# design.net
KiCad netlist of a schematic drawn in EasyEDA Pro
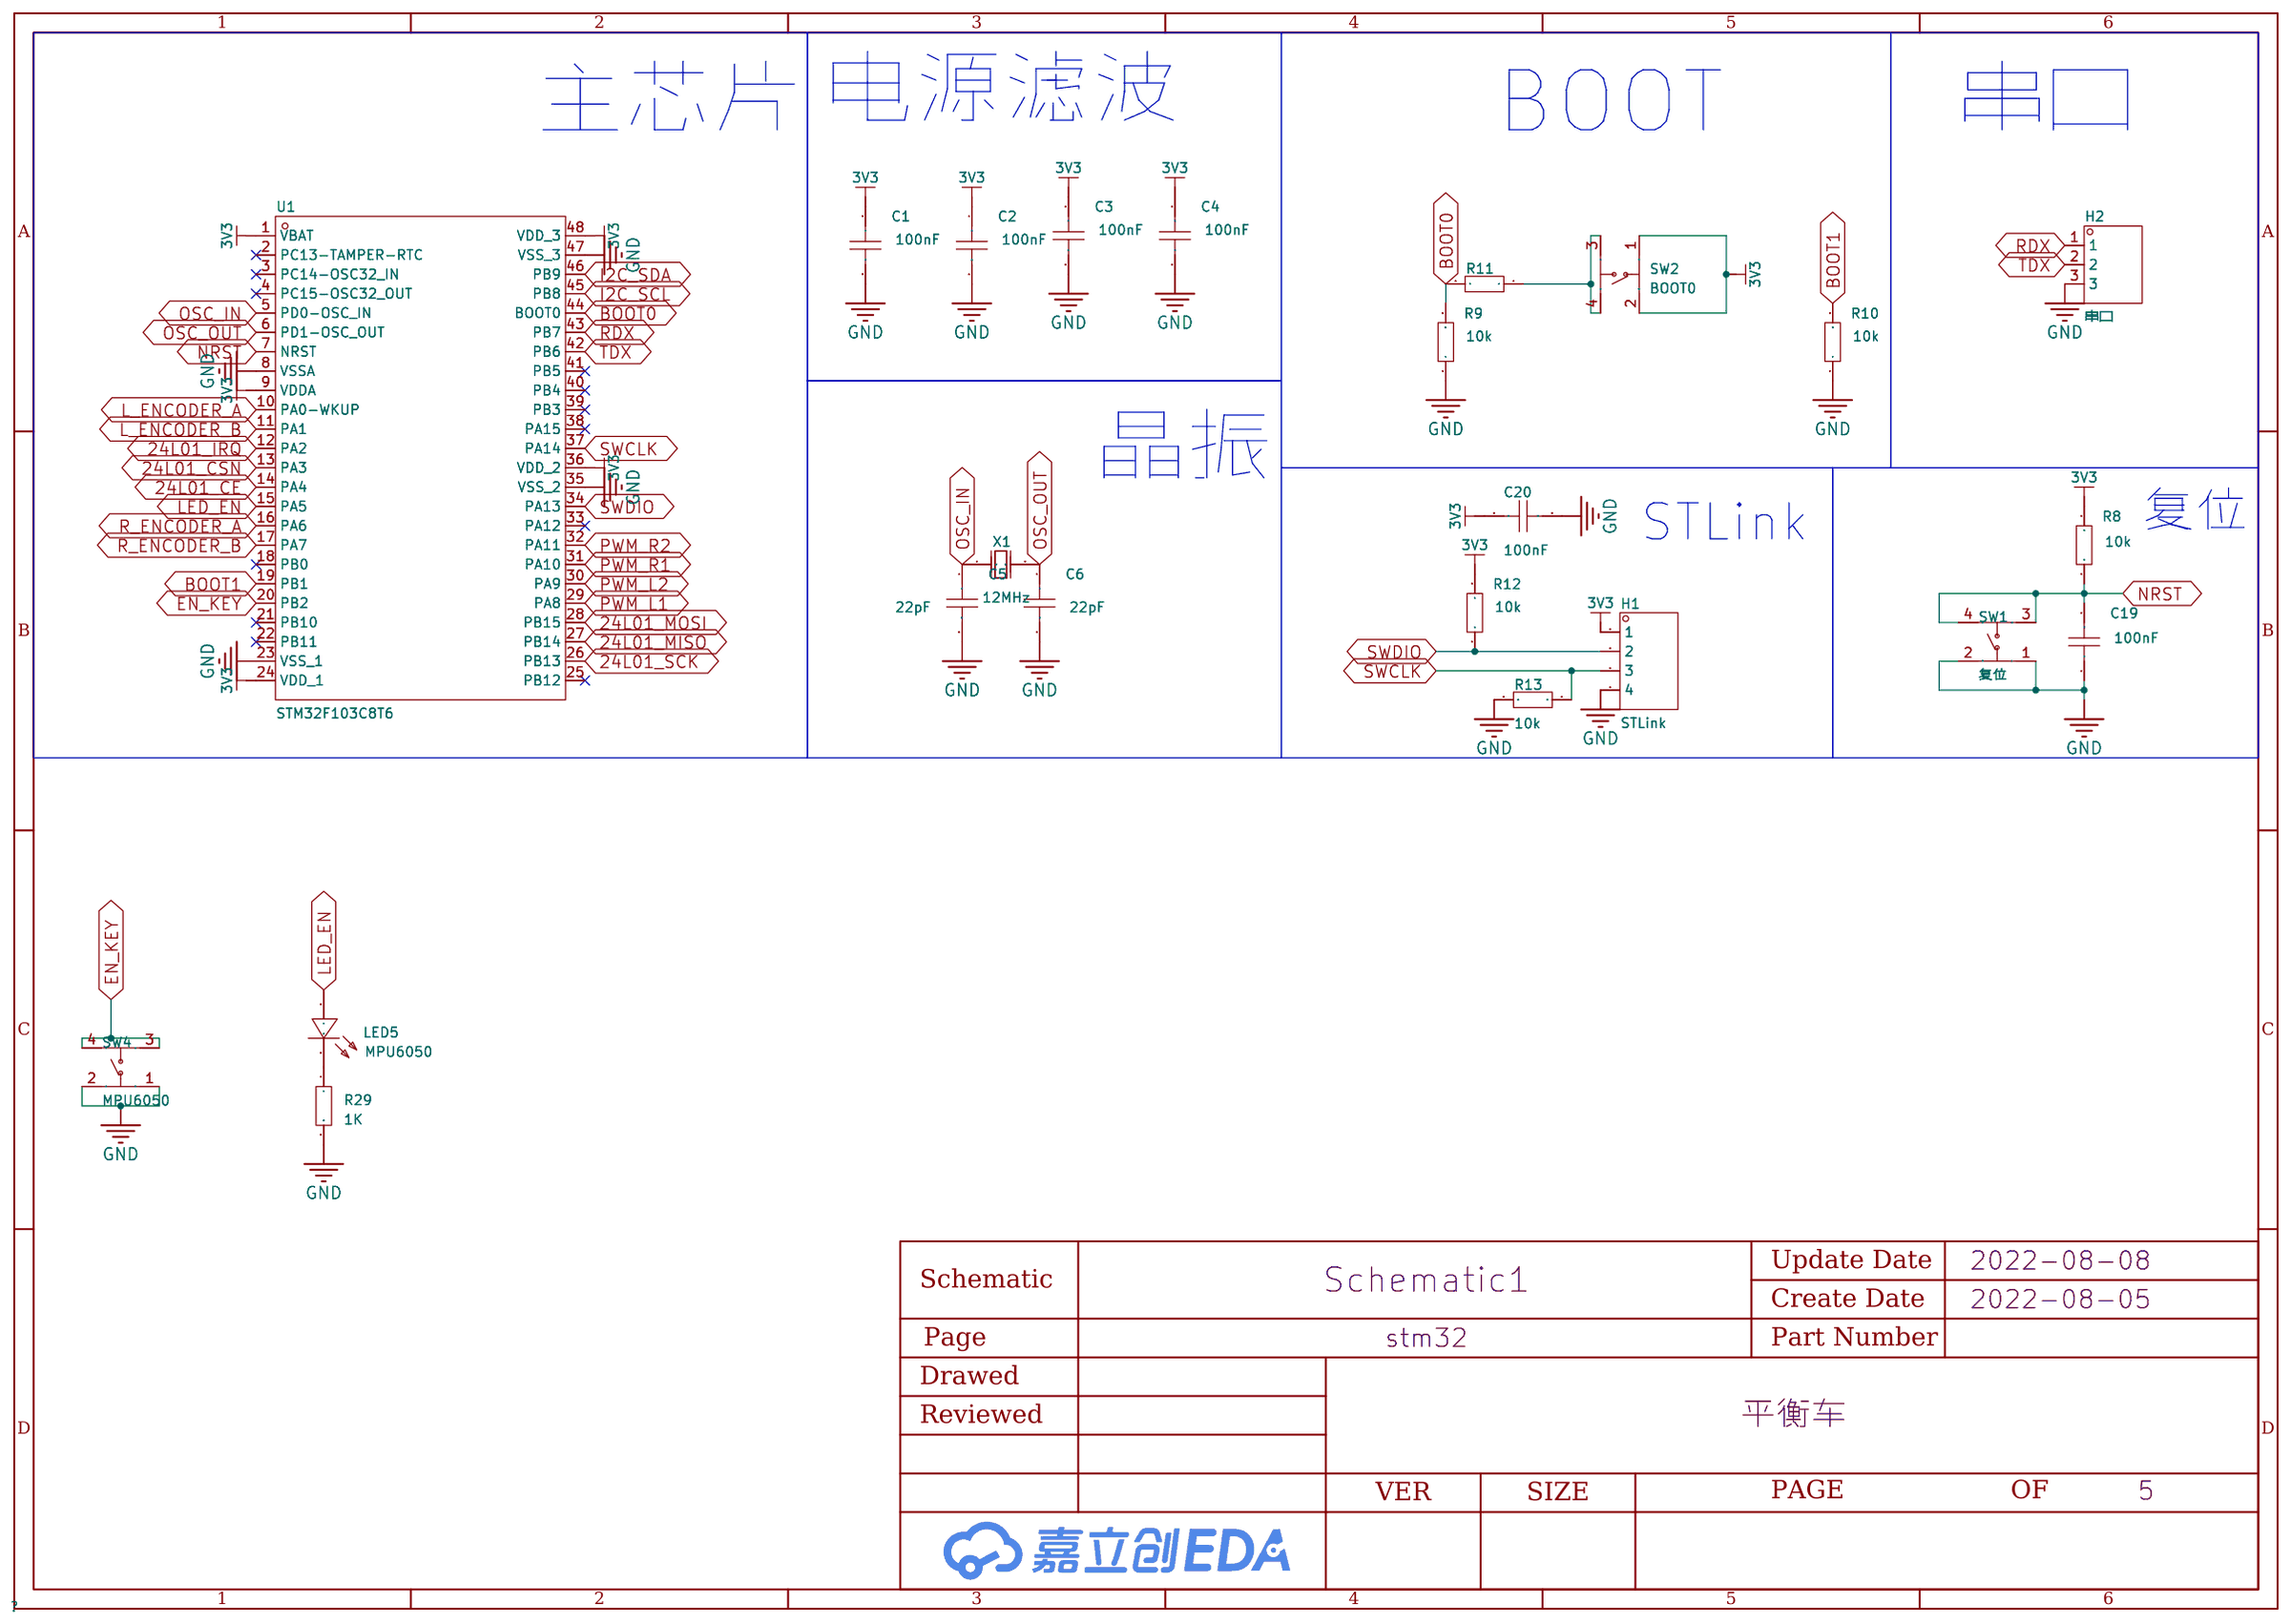
[diagram p0: stm32]
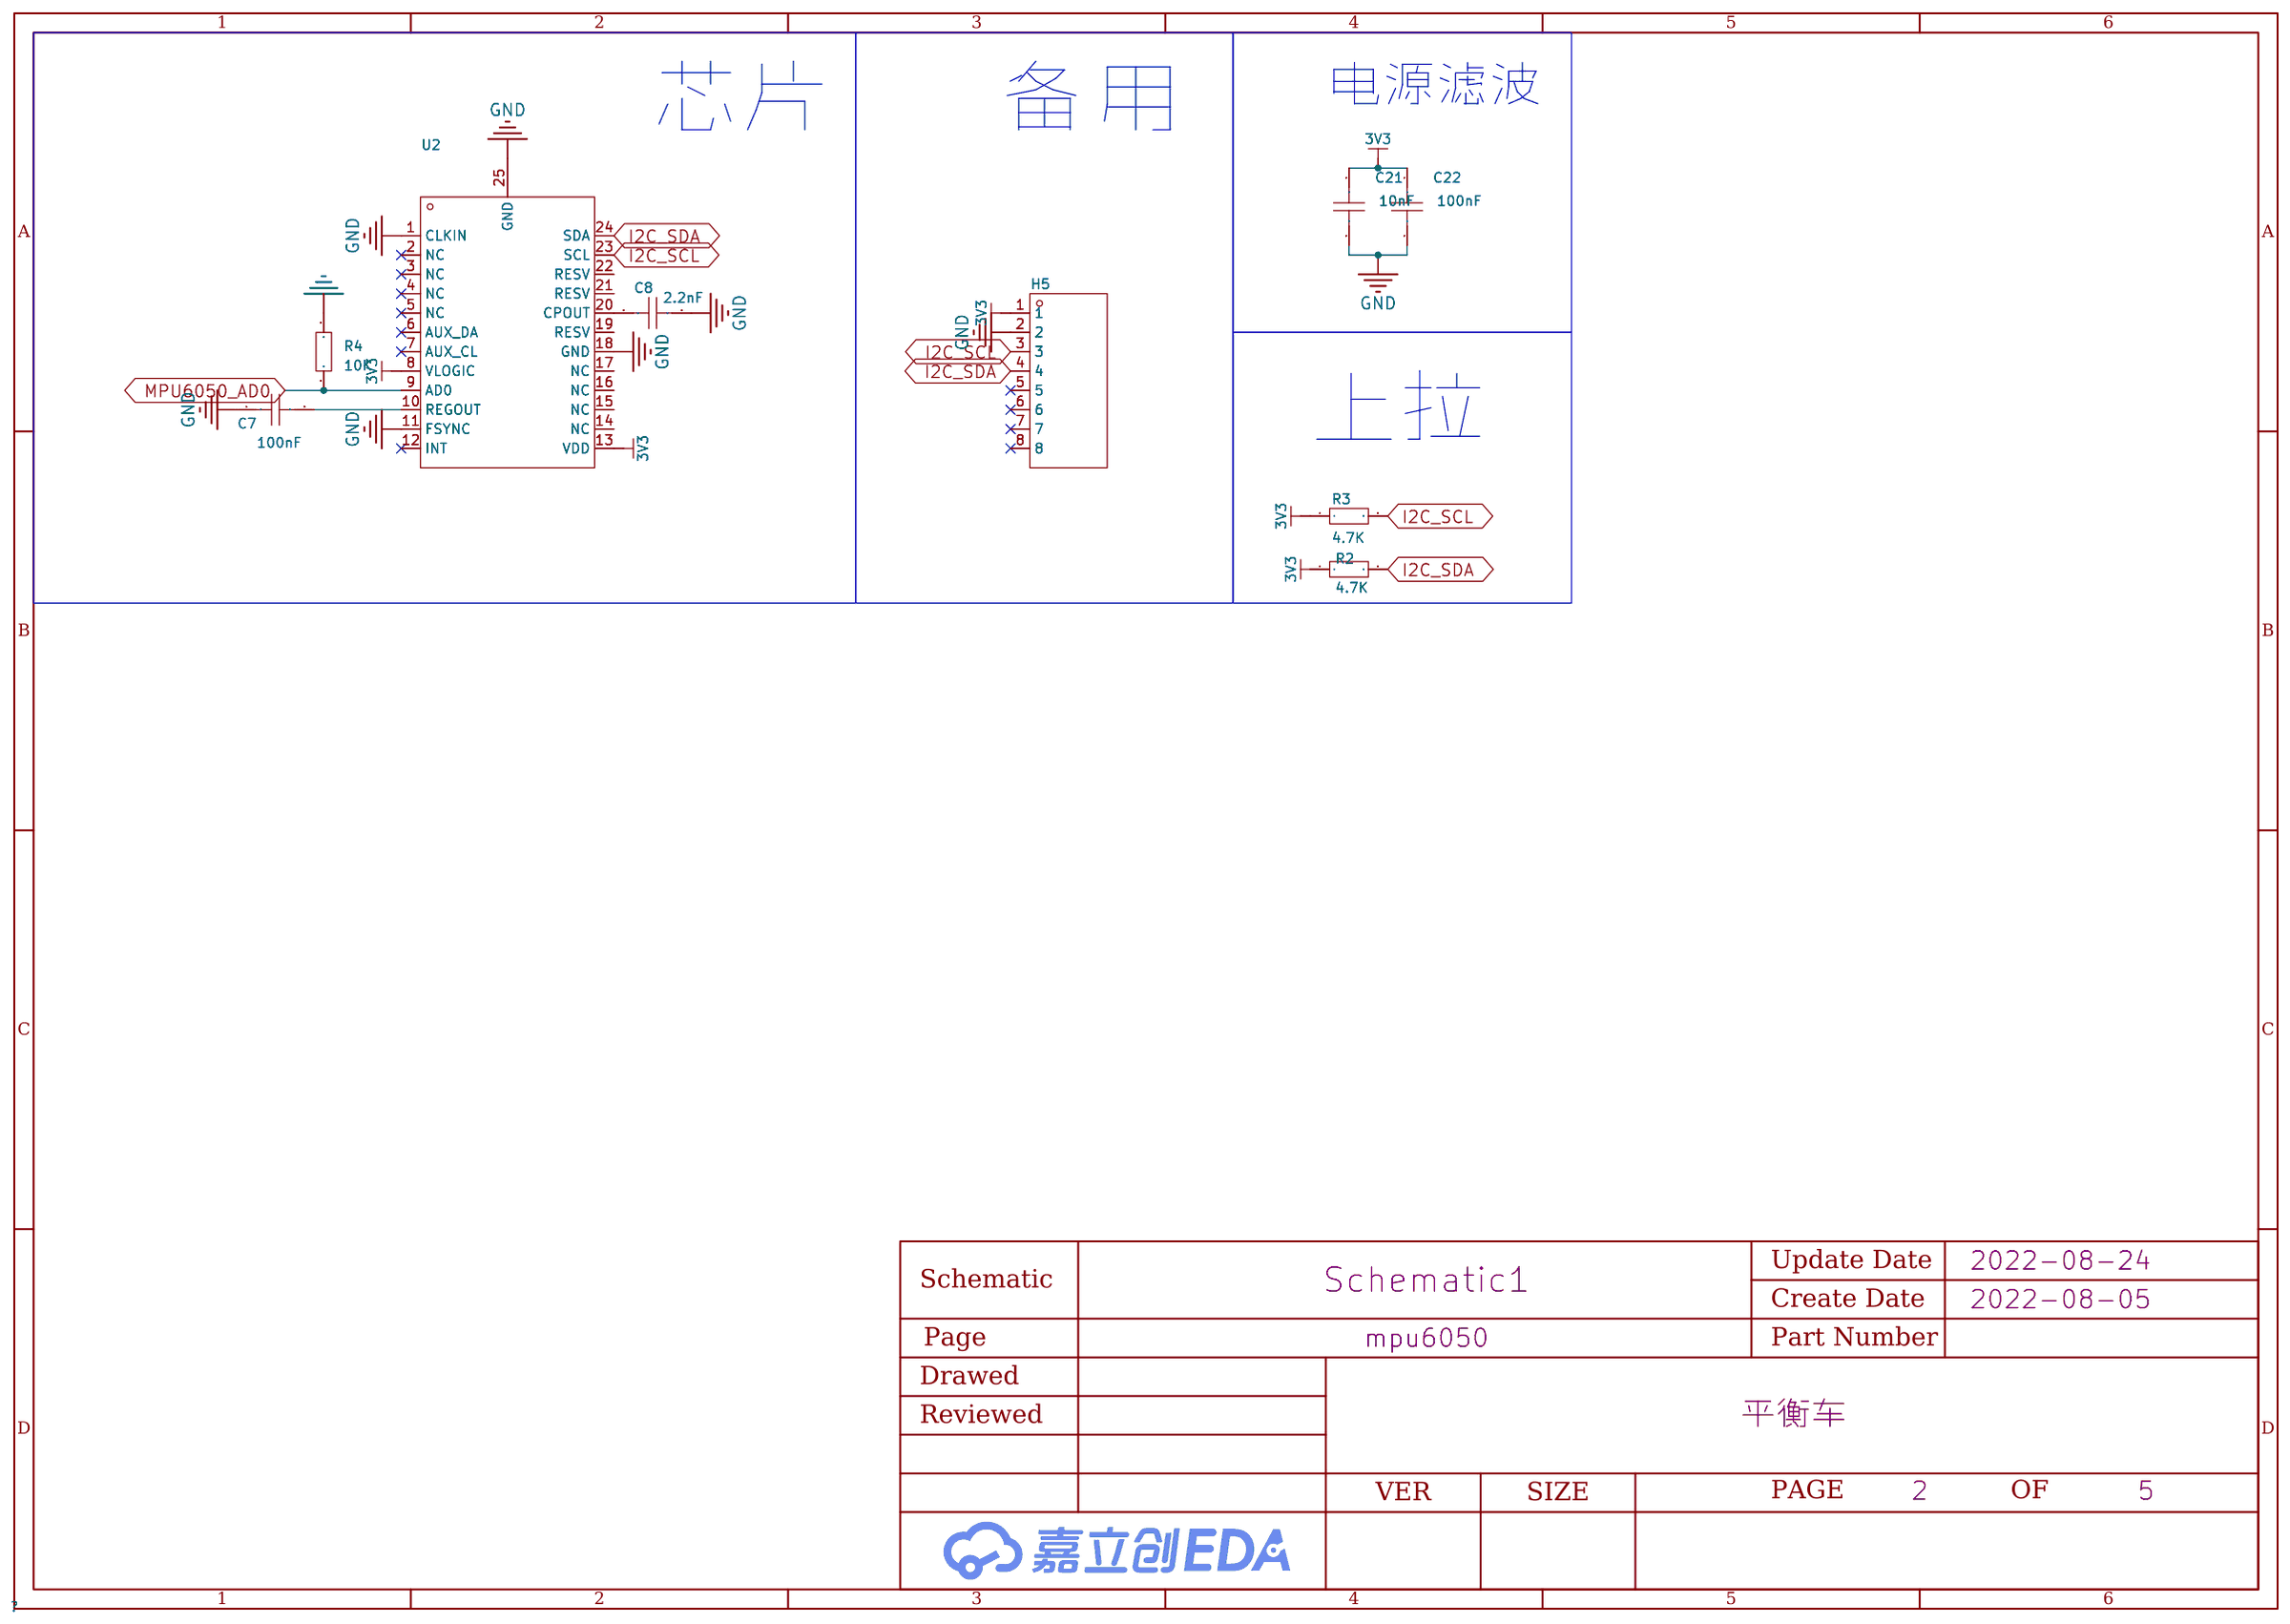
[diagram p1: mpu6050]
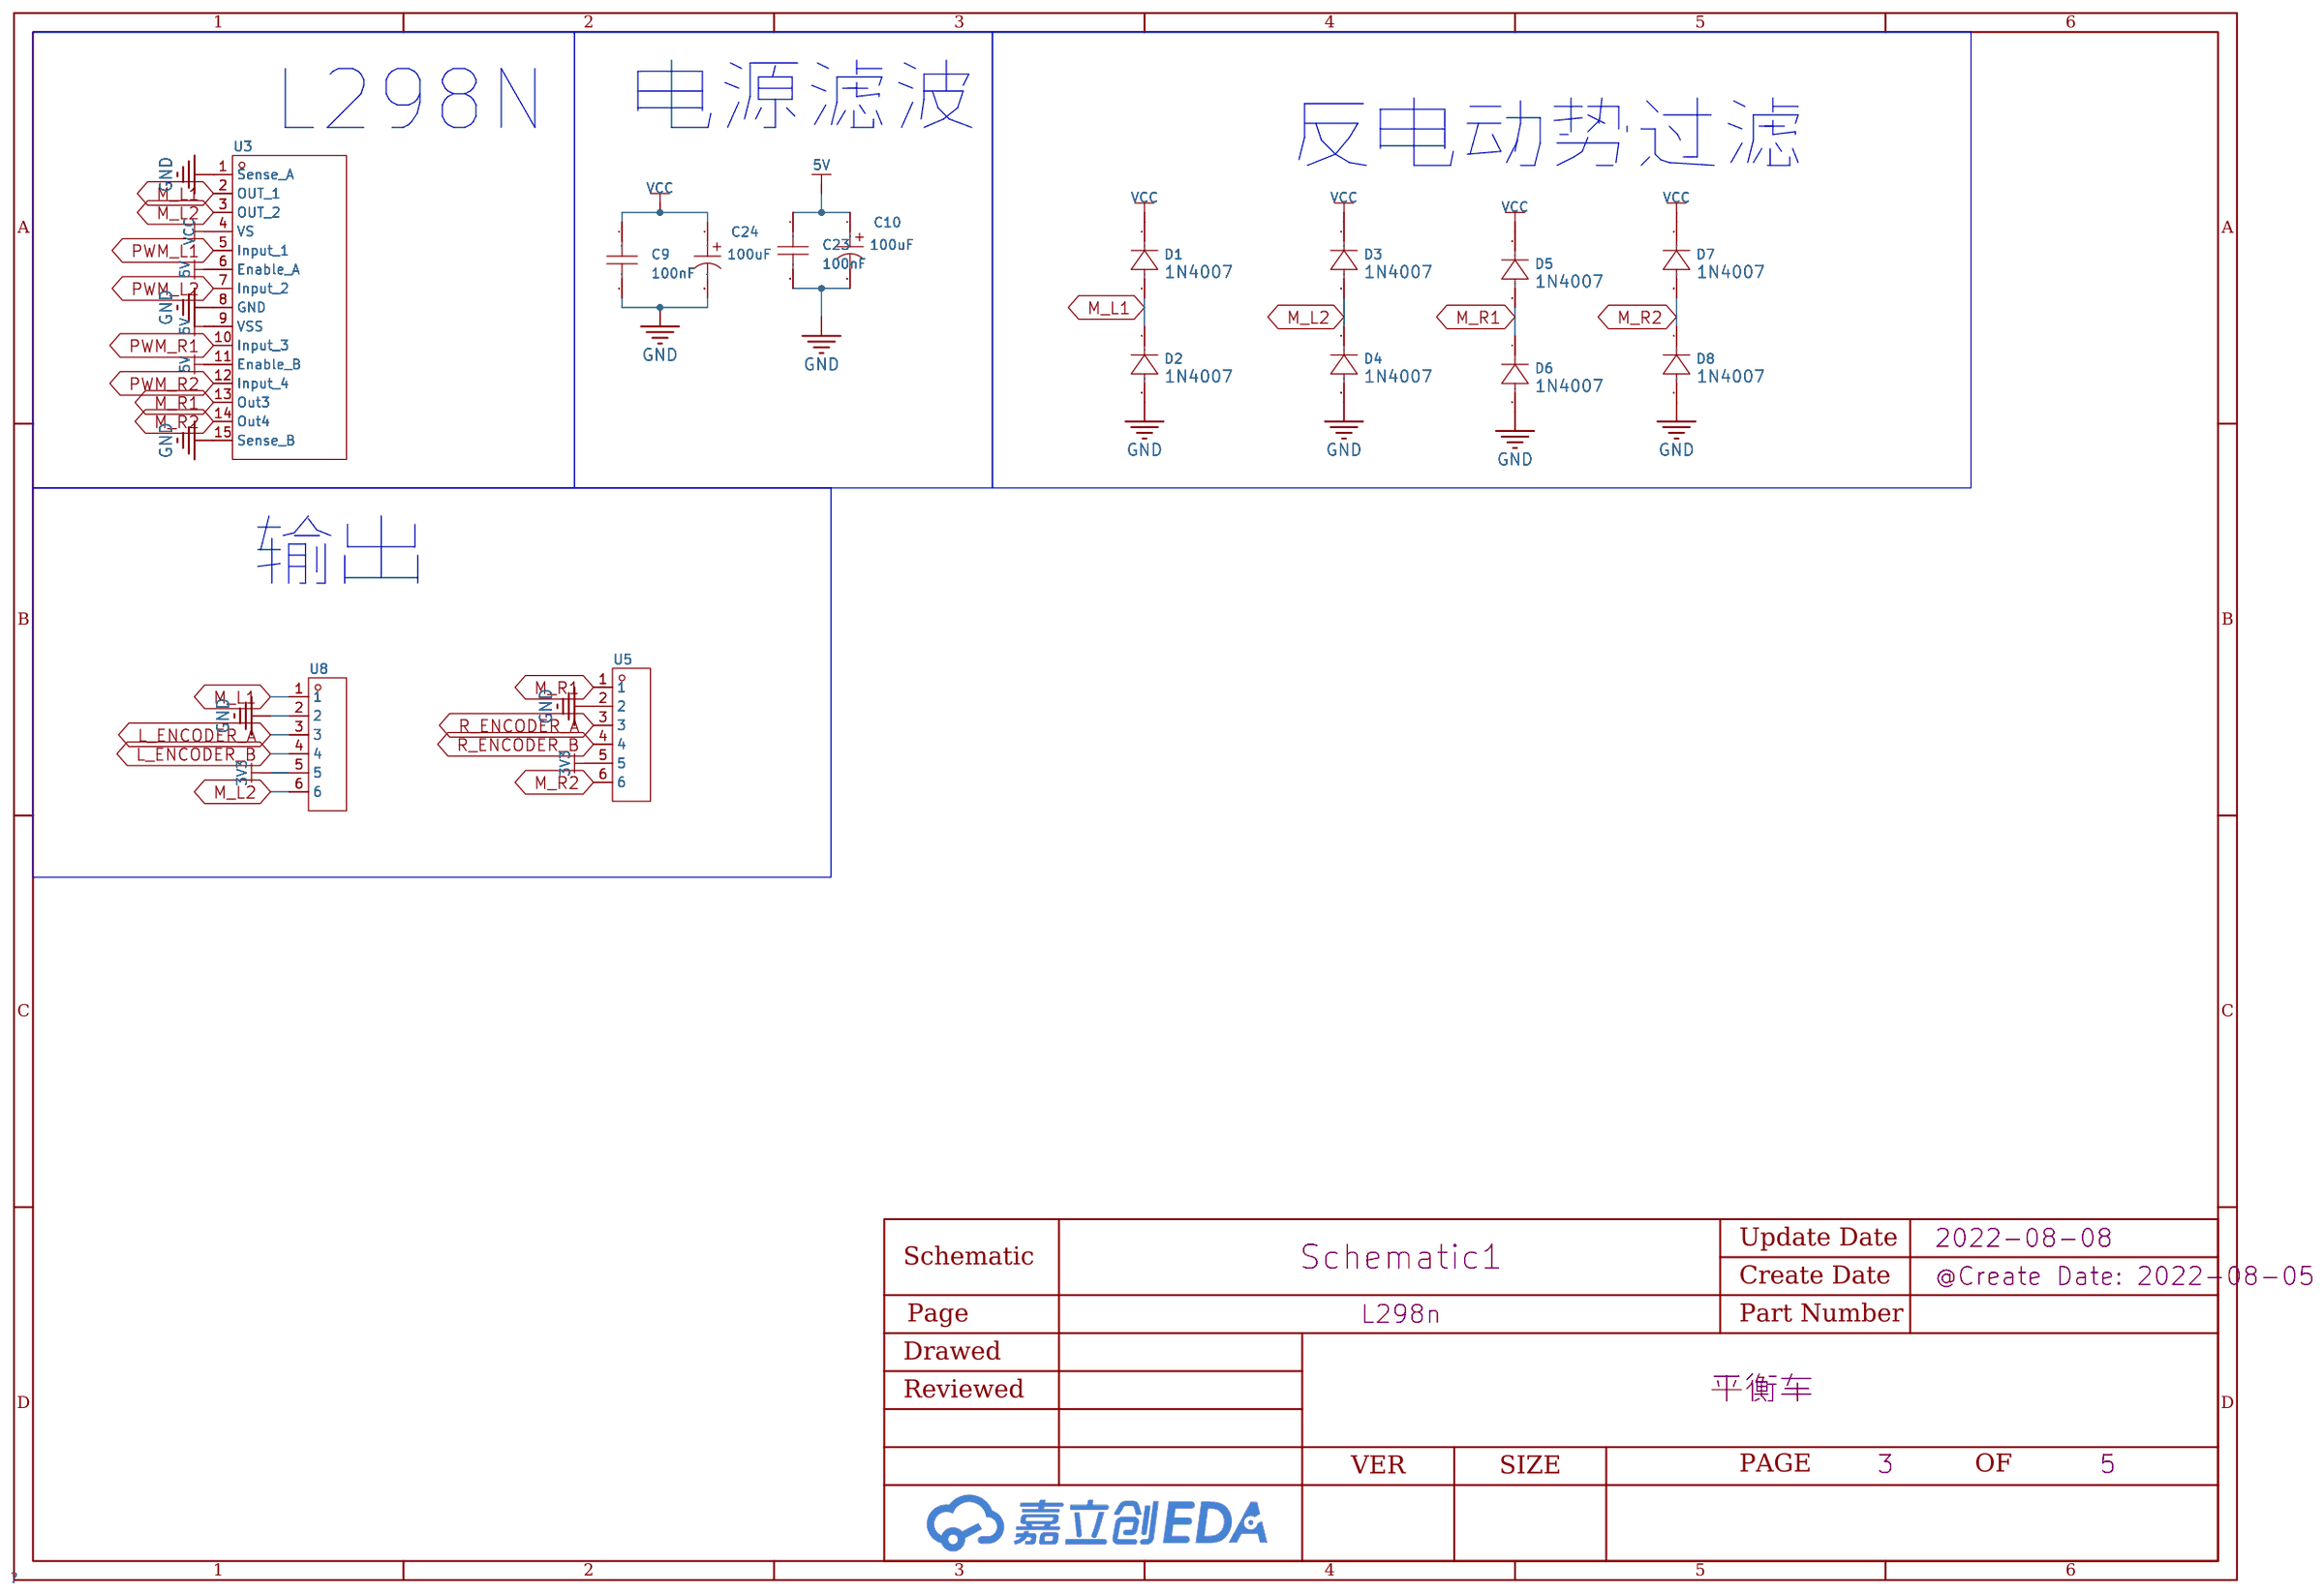
[diagram p2: L298n]
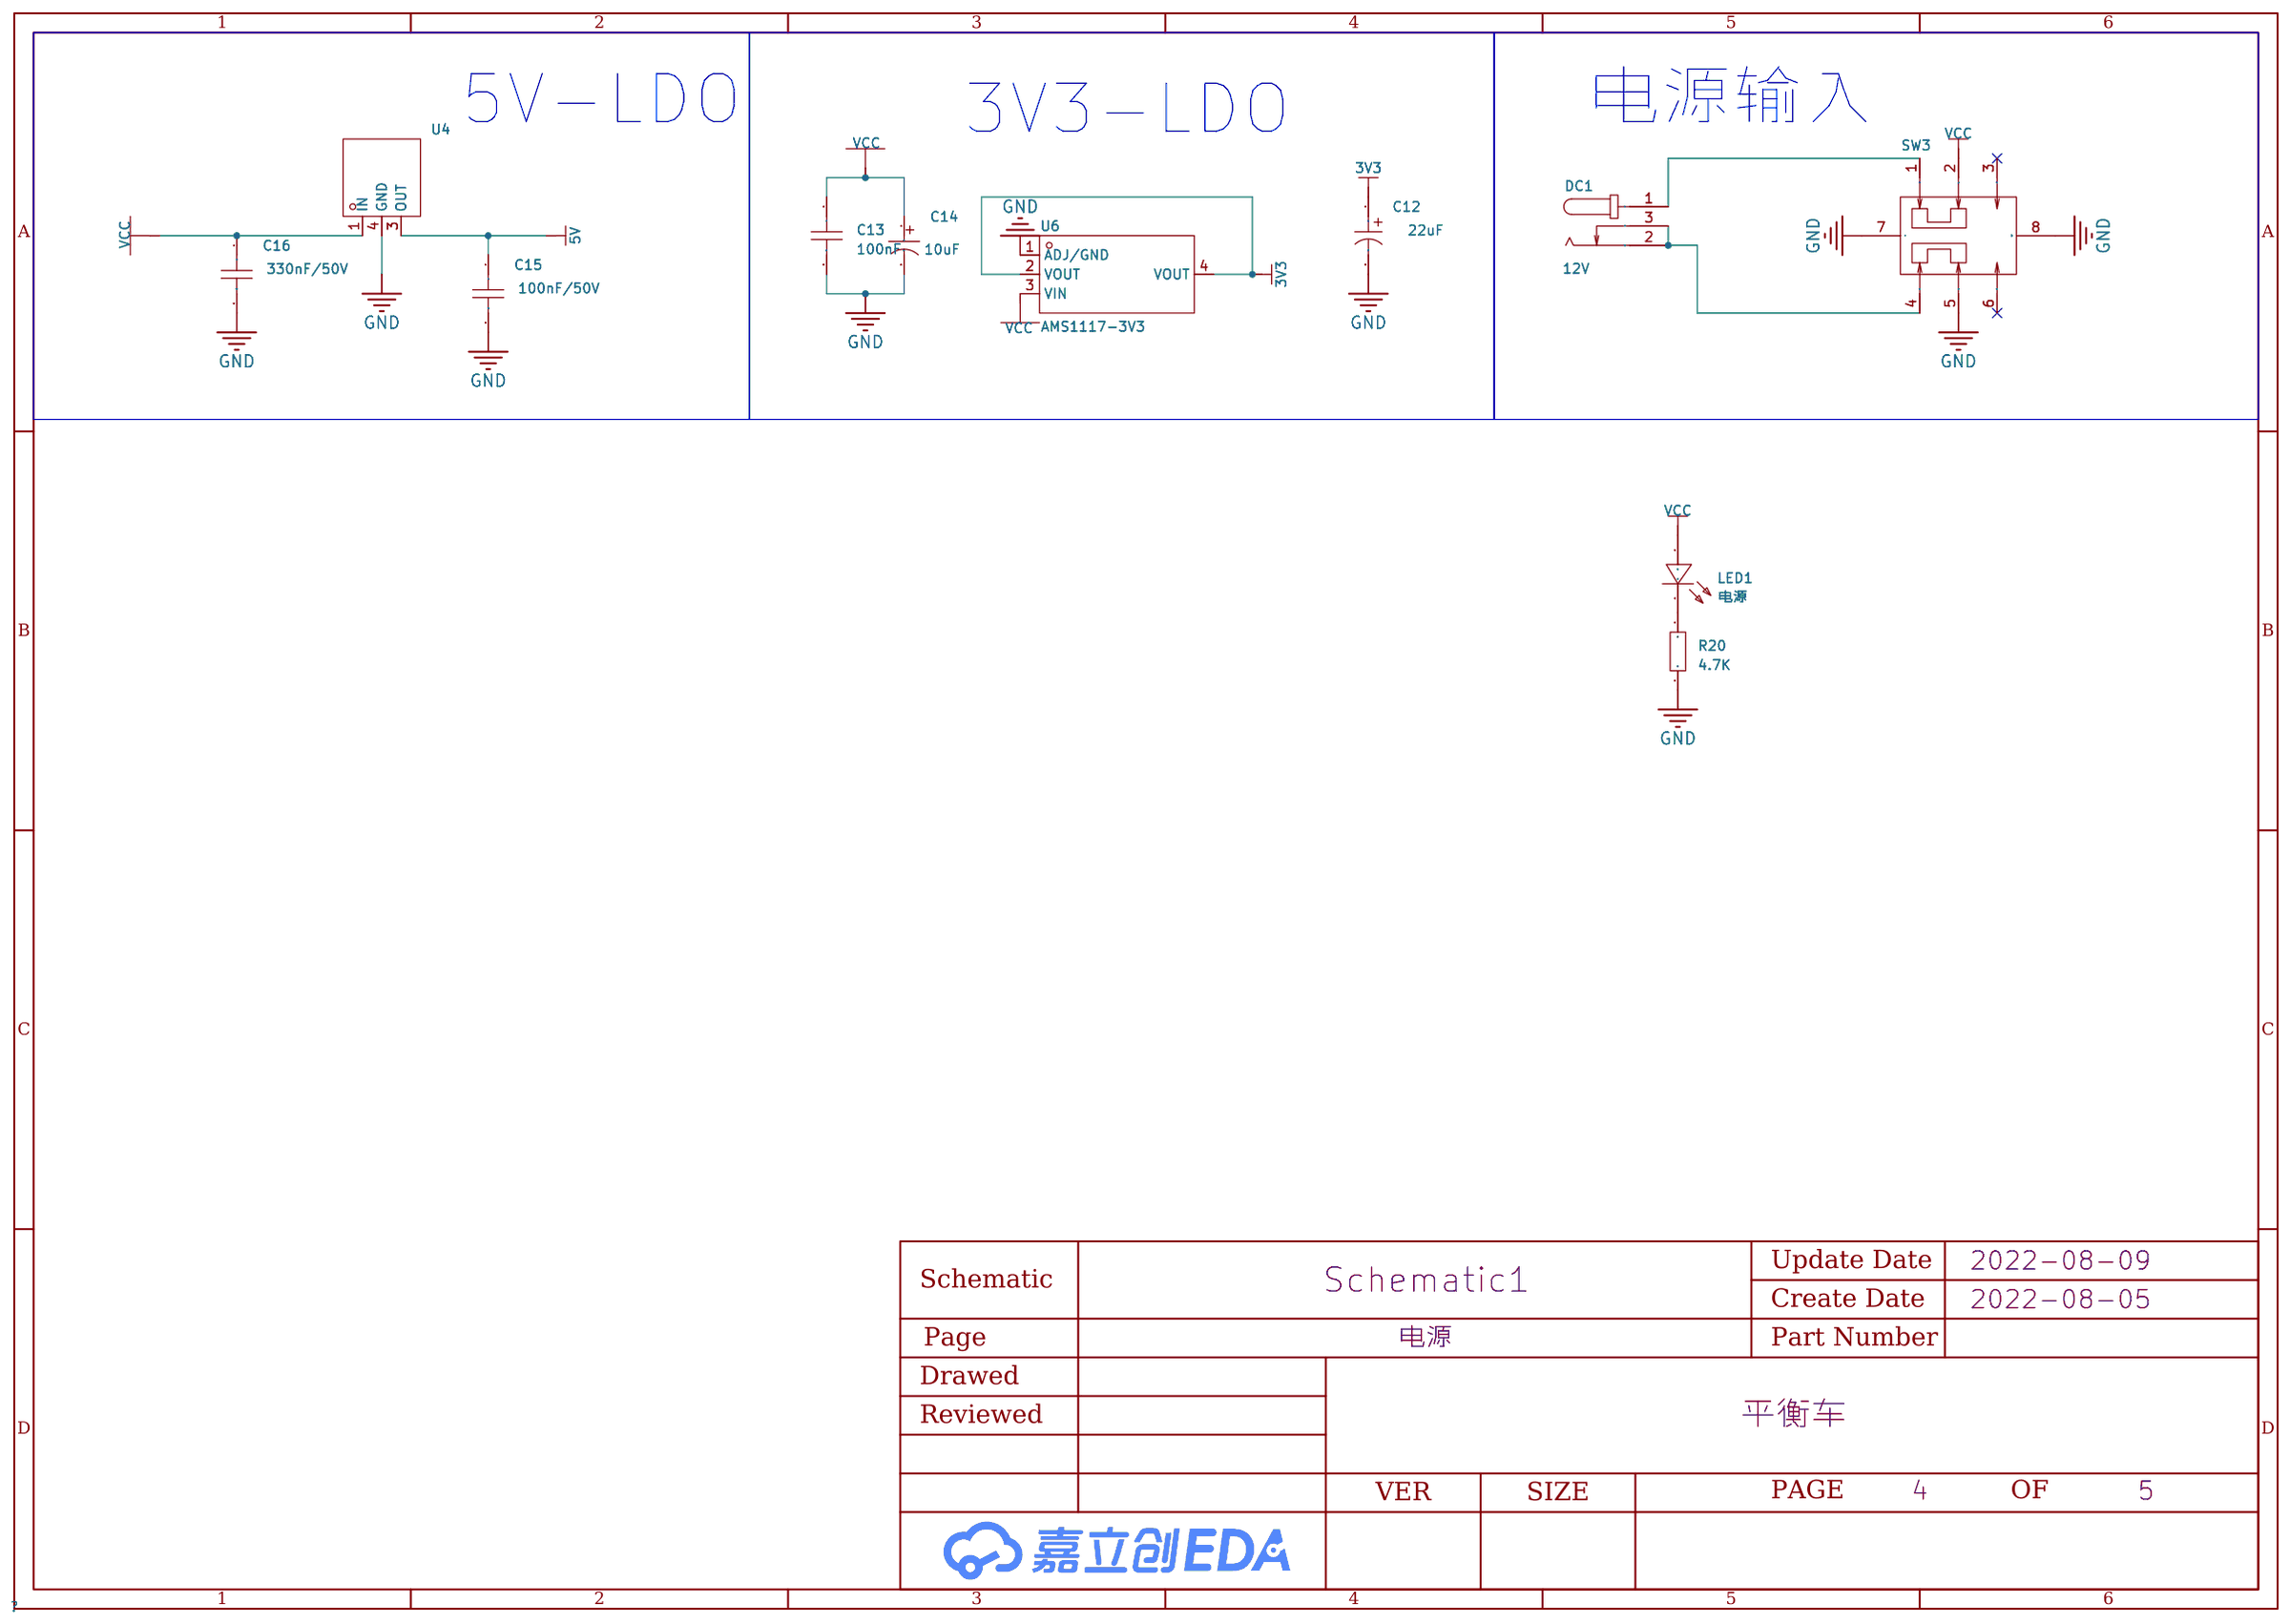
[diagram p3: 电源]
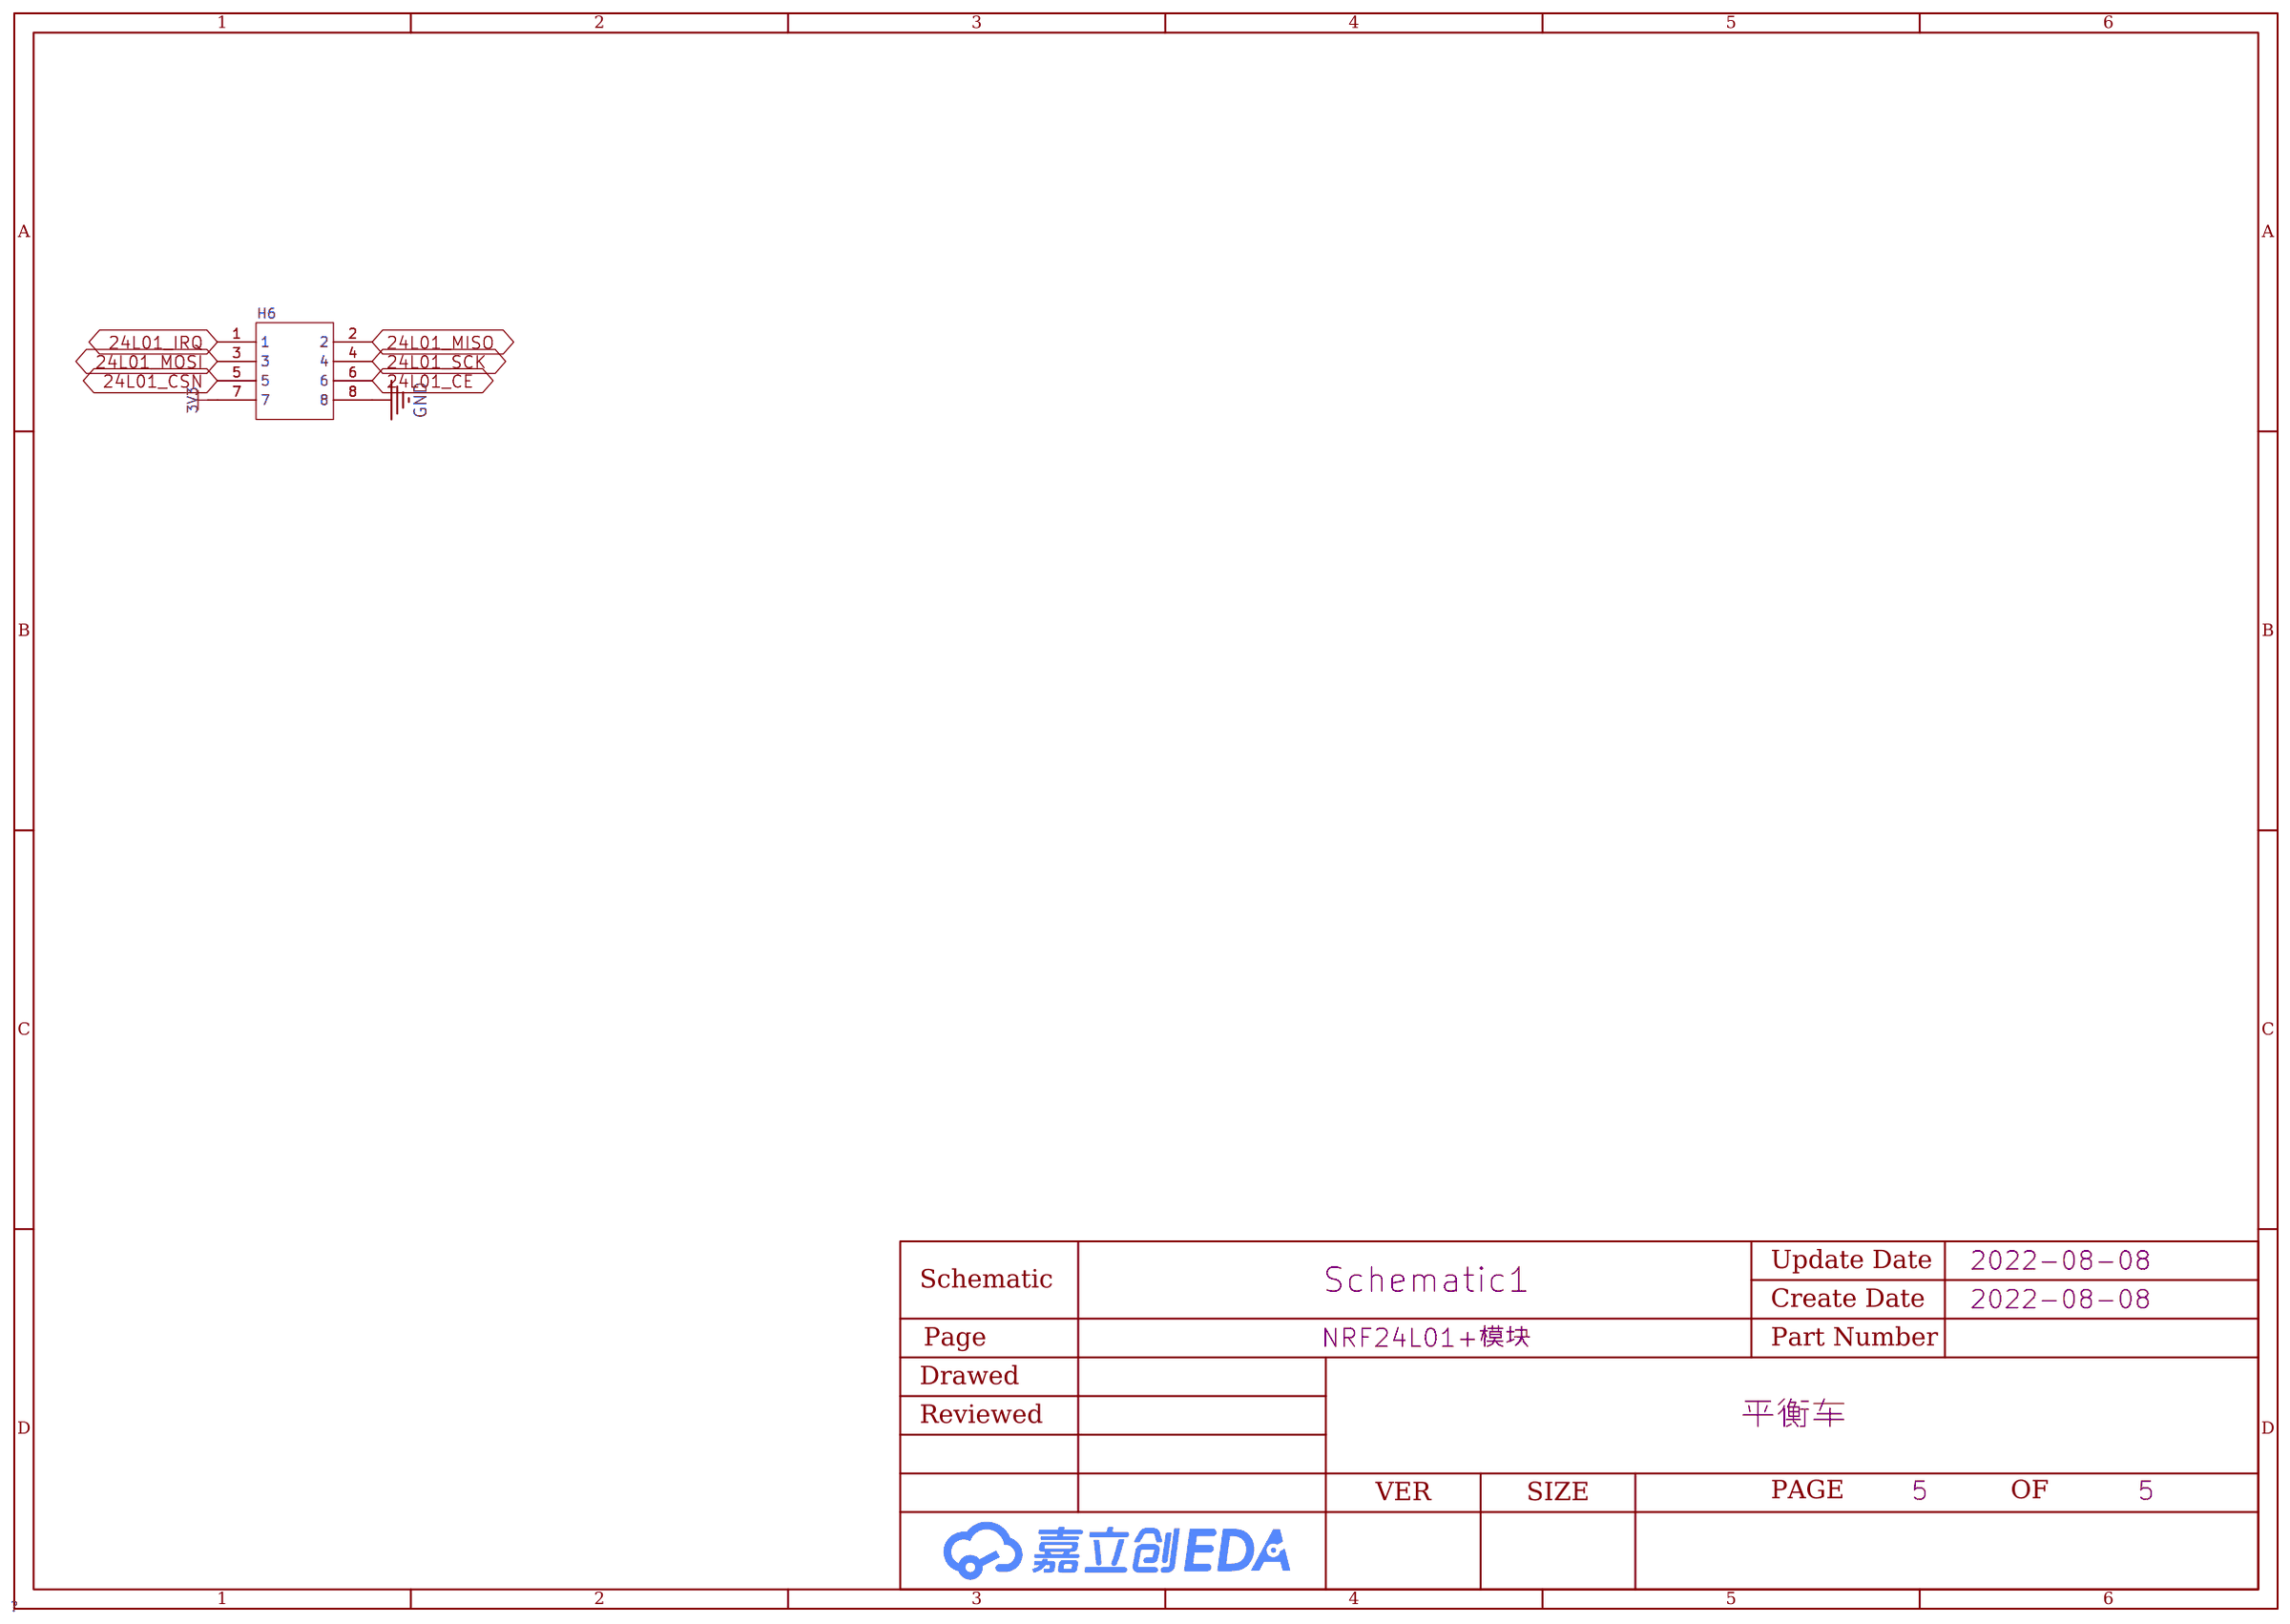
[diagram p4: NRF24L01+模块]

(export (version "E")
  (design (tool "Eeschema 10.0.6"))
  (components
    (comp (ref "C1")
      (value "100nF")
      (footprint "easyedapro:C0805")
      (fields (field (name "Manufacturer Part") "0805"))
      (libsource (lib "easyedapro") (part "0805_C9900012713"))
    )
    (comp (ref "C2")
      (value "100nF")
      (footprint "easyedapro:C0805")
      (fields (field (name "Manufacturer Part") "0805"))
      (libsource (lib "easyedapro") (part "0805_C9900012713"))
    )
    (comp (ref "C3")
      (value "100nF")
      (footprint "easyedapro:C0805")
      (fields (field (name "Manufacturer Part") "0805"))
      (libsource (lib "easyedapro") (part "0805_C9900012713"))
    )
    (comp (ref "C4")
      (value "100nF")
      (footprint "easyedapro:C0805")
      (fields (field (name "Manufacturer Part") "0805"))
      (libsource (lib "easyedapro") (part "0805_C9900012713"))
    )
    (comp (ref "C5")
      (value "22pF")
      (footprint "easyedapro:C0805")
      (fields (field (name "Manufacturer Part") "0805"))
      (libsource (lib "easyedapro") (part "0805_C9900012713"))
    )
    (comp (ref "C6")
      (value "22pF")
      (footprint "easyedapro:C0805")
      (fields (field (name "Manufacturer Part") "0805"))
      (libsource (lib "easyedapro") (part "0805_C9900012713"))
    )
    (comp (ref "C19")
      (value "100nF")
      (footprint "easyedapro:C0805")
      (fields (field (name "Manufacturer Part") "0805"))
      (libsource (lib "easyedapro") (part "0805_C9900012713"))
    )
    (comp (ref "C20")
      (value "100nF")
      (footprint "easyedapro:C0805")
      (fields (field (name "Manufacturer Part") "0805"))
      (libsource (lib "easyedapro") (part "0805_C9900012713"))
    )
    (comp (ref "H1")
      (value "STLink")
      (footprint "easyedapro:HDR-TH_4P-P2.54-V-M")
      (fields (field (name "Manufacturer Part") "B-2100S04P-A110") (field (name "Manufacturer") "Ckmtw(灿科盟)"))
      (libsource (lib "easyedapro") (part "Header-Male-2.54_1x4"))
    )
    (comp (ref "H2")
      (value "串口")
      (footprint "easyedapro:HDR-TH_3P-P2.54-V-M-1")
      (fields (field (name "Manufacturer Part") "77311-102-03LF") (field (name "Manufacturer") "Amphenol"))
      (libsource (lib "easyedapro") (part "77311-102-03LF"))
    )
    (comp (ref "LED5")
      (value "MPU6050")
      (footprint "easyedapro:LED0805-R-RD")
      (description "发光颜色:翠绿;")
      (fields (field (name "Manufacturer Part") "NCD0805G1") (field (name "Manufacturer") "国星光电"))
      (libsource (lib "easyedapro") (part "FC-2012UGK-520D5"))
    )
    (comp (ref "R8")
      (value "10k")
      (footprint "easyedapro:R0805")
      (fields (field (name "Manufacturer Part") "0805"))
      (libsource (lib "easyedapro") (part "0805"))
    )
    (comp (ref "R9")
      (value "10k")
      (footprint "easyedapro:R0805")
      (fields (field (name "Manufacturer Part") "0805"))
      (libsource (lib "easyedapro") (part "0805"))
    )
    (comp (ref "R10")
      (value "10k")
      (footprint "easyedapro:R0805")
      (fields (field (name "Manufacturer Part") "0805"))
      (libsource (lib "easyedapro") (part "0805"))
    )
    (comp (ref "R11")
      (value "100R")
      (footprint "easyedapro:R0805")
      (fields (field (name "Manufacturer Part") "0805"))
      (libsource (lib "easyedapro") (part "0805"))
    )
    (comp (ref "R12")
      (value "10k")
      (footprint "easyedapro:R0805")
      (fields (field (name "Manufacturer Part") "0805"))
      (libsource (lib "easyedapro") (part "0805"))
    )
    (comp (ref "R13")
      (value "10k")
      (footprint "easyedapro:R0805")
      (fields (field (name "Manufacturer Part") "0805"))
      (libsource (lib "easyedapro") (part "0805"))
    )
    (comp (ref "R29")
      (value "1K")
      (footprint "easyedapro:R0805")
      (fields (field (name "Manufacturer Part") "0805"))
      (libsource (lib "easyedapro") (part "0805"))
    )
    (comp (ref "SW1")
      (value "复位")
      (footprint "easyedapro:SW-SMD_4P-L6.0-W6.0-P4.50-LS9.0-2")
      (fields
        (field (name "Manufacturer Part") "KH-6X6X5H-STM")
        (field (name "Manufacturer") "kinghelm(金航标)")
      )
      (libsource (lib "easyedapro") (part "KH-6X6X5H-STM"))
    )
    (comp (ref "SW2")
      (value "BOOT0")
      (footprint "easyedapro:SW-SMD_4P-L6.0-W6.0-P4.50-LS9.0-2")
      (fields
        (field (name "Manufacturer Part") "KH-6X6X5H-STM")
        (field (name "Manufacturer") "kinghelm(金航标)")
      )
      (libsource (lib "easyedapro") (part "KH-6X6X5H-STM"))
    )
    (comp (ref "SW4")
      (value "MPU6050")
      (footprint "easyedapro:SW-SMD_4P-L6.0-W6.0-P4.50-LS9.0-2")
      (fields
        (field (name "Manufacturer Part") "KH-6X6X5H-STM")
        (field (name "Manufacturer") "kinghelm(金航标)")
      )
      (libsource (lib "easyedapro") (part "KH-6X6X5H-STM"))
    )
    (comp (ref "U1")
      (value "STM32F103C8T6")
      (footprint "easyedapro:LQFP-48_L7.0-W7.0-P0.50-LS9.0-BL")
      (description "CPU位数:32-Bit;ROM类型:FLASH;CPU内核:ARM® Cortex®-M3;主频（MAX):72MHz;工作电压:2V ~ 3.6V;")
      (fields (field (name "Manufacturer") "ST(意法半导体)"))
      (libsource (lib "easyedapro") (part "STM32F103C8T6"))
    )
    (comp (ref "X1")
      (value "12MHz")
      (footprint "easyedapro:HC-49S_L11.4-W4.8")
      (description "晶振类型:-;频率:-;频率公差:-;负载电容:-;工作温度:-;")
      (fields (field (name "Manufacturer Part") "HCM4916000000ABJT") (field (name "Manufacturer") "CITIZEN"))
      (libsource (lib "easyedapro") (part "HCM4916000000ABJT"))
    )
    (comp (ref "C7")
      (value "100nF")
      (footprint "easyedapro:C0805")
      (fields (field (name "Manufacturer Part") "0805"))
      (libsource (lib "easyedapro") (part "0805_C9900012713"))
    )
    (comp (ref "C8")
      (value "2.2nF")
      (footprint "easyedapro:C0805")
      (fields (field (name "Manufacturer Part") "0805"))
      (libsource (lib "easyedapro") (part "0805_C9900012713"))
    )
    (comp (ref "C21")
      (value "10nF")
      (footprint "easyedapro:C0805")
      (fields (field (name "Manufacturer Part") "0805"))
      (libsource (lib "easyedapro") (part "0805_C9900012713"))
    )
    (comp (ref "C22")
      (value "100nF")
      (footprint "easyedapro:C0805")
      (fields (field (name "Manufacturer Part") "0805"))
      (libsource (lib "easyedapro") (part "0805_C9900012713"))
    )
    (comp (ref "H5")
      (value "A2541HWV-8P")
      (footprint "easyedapro:HDR-TH_8P-P2.54-V_A2541HWV-8P")
      (description "间距:2.54mm;总孔位数:8;排数:1;插孔结构:1x8P;行距:-;安装类型:直插;塑高:-;触头材质:黄铜;触头镀层:金;")
      (fields (field (name "Manufacturer") "CJT(长江连接器)"))
      (libsource (lib "easyedapro") (part "A2541HWV-8P"))
    )
    (comp (ref "R2")
      (value "4.7K")
      (footprint "easyedapro:R0805")
      (fields (field (name "Manufacturer Part") "0805"))
      (libsource (lib "easyedapro") (part "0805"))
    )
    (comp (ref "R3")
      (value "4.7K")
      (footprint "easyedapro:R0805")
      (fields (field (name "Manufacturer Part") "0805"))
      (libsource (lib "easyedapro") (part "0805"))
    )
    (comp (ref "R4")
      (value "10K")
      (footprint "easyedapro:R0805")
      (fields (field (name "Manufacturer Part") "0805"))
      (libsource (lib "easyedapro") (part "0805"))
    )
    (comp (ref "U2")
      (value "~")
      (footprint "easyedapro:QFN-24_L4.0-W4.0-P0.50-BL-EP2.7")
      (description "三轴加速度计和三轴陀螺仪，工作电压：2.375V~3.46V")
      (fields
        (field (name "Manufacturer Part") "MPU-6050")
        (field (name "Manufacturer") "TDK InvenSense(应美盛)")
      )
      (libsource (lib "easyedapro") (part "MPU-6050_C24112"))
    )
    (comp (ref "C9")
      (value "100nF")
      (footprint "easyedapro:C0805")
      (fields (field (name "Manufacturer Part") "0805"))
      (libsource (lib "easyedapro") (part "0805_C9900012713"))
    )
    (comp (ref "C10")
      (value "100uF")
      (footprint "easyedapro:CAP-TH_BD8.0-P3.50-D0.6-FD")
      (description "容值:100uF;精度:-;额定电压:50V;电容体直径:-;电容体长度:-;脚间距:-;纹波电流:-;等效串联电阻:-;工作寿命:-;工作温度:-;")
      (fields (field (name "Manufacturer Part") "EEUFR1H101B") (field (name "Manufacturer") "PANASONIC(松下)"))
      (libsource (lib "easyedapro") (part "EEUFR1H101B"))
    )
    (comp (ref "C23")
      (value "100nF")
      (footprint "easyedapro:C0805")
      (fields (field (name "Manufacturer Part") "0805"))
      (libsource (lib "easyedapro") (part "0805_C9900012713"))
    )
    (comp (ref "C24")
      (value "100uF")
      (footprint "easyedapro:CAP-TH_BD8.0-P3.50-D0.6-FD")
      (description "容值:100uF;精度:-;额定电压:50V;电容体直径:-;电容体长度:-;脚间距:-;纹波电流:-;等效串联电阻:-;工作寿命:-;工作温度:-;")
      (fields (field (name "Manufacturer Part") "EEUFR1H101B") (field (name "Manufacturer") "PANASONIC(松下)"))
      (libsource (lib "easyedapro") (part "EEUFR1H101B"))
    )
    (comp (ref "D1")
      (value "1N4007")
      (footprint "easyedapro:SMA_L4.4-W2.8-LS5.4-RD")
      (description "二极管配置:独立式;直流反向耐压(Vr):1kV;平均整流电流(Io):1A;正向压降(Vf):1.1V@1A;反向电流(Ir):5A@1kV;")
      (fields (field (name "Manufacturer") "TWGMC(台湾迪嘉)"))
      (libsource (lib "easyedapro") (part "1N4007_C727081"))
    )
    (comp (ref "D2")
      (value "1N4007")
      (footprint "easyedapro:SMA_L4.4-W2.8-LS5.4-RD")
      (description "二极管配置:独立式;直流反向耐压(Vr):1kV;平均整流电流(Io):1A;正向压降(Vf):1.1V@1A;反向电流(Ir):5A@1kV;")
      (fields (field (name "Manufacturer") "TWGMC(台湾迪嘉)"))
      (libsource (lib "easyedapro") (part "1N4007_C727081"))
    )
    (comp (ref "D3")
      (value "1N4007")
      (footprint "easyedapro:SMA_L4.4-W2.8-LS5.4-RD")
      (description "二极管配置:独立式;直流反向耐压(Vr):1kV;平均整流电流(Io):1A;正向压降(Vf):1.1V@1A;反向电流(Ir):5A@1kV;")
      (fields (field (name "Manufacturer") "TWGMC(台湾迪嘉)"))
      (libsource (lib "easyedapro") (part "1N4007_C727081"))
    )
    (comp (ref "D4")
      (value "1N4007")
      (footprint "easyedapro:SMA_L4.4-W2.8-LS5.4-RD")
      (description "二极管配置:独立式;直流反向耐压(Vr):1kV;平均整流电流(Io):1A;正向压降(Vf):1.1V@1A;反向电流(Ir):5A@1kV;")
      (fields (field (name "Manufacturer") "TWGMC(台湾迪嘉)"))
      (libsource (lib "easyedapro") (part "1N4007_C727081"))
    )
    (comp (ref "D5")
      (value "1N4007")
      (footprint "easyedapro:SMA_L4.4-W2.8-LS5.4-RD")
      (description "二极管配置:独立式;直流反向耐压(Vr):1kV;平均整流电流(Io):1A;正向压降(Vf):1.1V@1A;反向电流(Ir):5A@1kV;")
      (fields (field (name "Manufacturer") "TWGMC(台湾迪嘉)"))
      (libsource (lib "easyedapro") (part "1N4007_C727081"))
    )
    (comp (ref "D6")
      (value "1N4007")
      (footprint "easyedapro:SMA_L4.4-W2.8-LS5.4-RD")
      (description "二极管配置:独立式;直流反向耐压(Vr):1kV;平均整流电流(Io):1A;正向压降(Vf):1.1V@1A;反向电流(Ir):5A@1kV;")
      (fields (field (name "Manufacturer") "TWGMC(台湾迪嘉)"))
      (libsource (lib "easyedapro") (part "1N4007_C727081"))
    )
    (comp (ref "D7")
      (value "1N4007")
      (footprint "easyedapro:SMA_L4.4-W2.8-LS5.4-RD")
      (description "二极管配置:独立式;直流反向耐压(Vr):1kV;平均整流电流(Io):1A;正向压降(Vf):1.1V@1A;反向电流(Ir):5A@1kV;")
      (fields (field (name "Manufacturer") "TWGMC(台湾迪嘉)"))
      (libsource (lib "easyedapro") (part "1N4007_C727081"))
    )
    (comp (ref "D8")
      (value "1N4007")
      (footprint "easyedapro:SMA_L4.4-W2.8-LS5.4-RD")
      (description "二极管配置:独立式;直流反向耐压(Vr):1kV;平均整流电流(Io):1A;正向压降(Vf):1.1V@1A;反向电流(Ir):5A@1kV;")
      (fields (field (name "Manufacturer") "TWGMC(台湾迪嘉)"))
      (libsource (lib "easyedapro") (part "1N4007_C727081"))
    )
    (comp (ref "U3")
      (value "~")
      (footprint "easyedapro:MULTIWATT-15_L19.6-W5.0-P1.27-L")
      (description "双全桥驱动IC")
      (fields (field (name "Manufacturer Part") "L298N") (field (name "Manufacturer") "ST(意法半导体)"))
      (libsource (lib "easyedapro") (part "L298N_C19922"))
    )
    (comp (ref "U5")
      (value "~")
      (footprint "easyedapro:CONN-TH_6P_PH2.0D-L-6P")
      (fields (field (name "Manufacturer Part") "PH2.0D-L-6P"))
      (libsource (lib "easyedapro") (part "PH2.0D-L-6P"))
    )
    (comp (ref "U8")
      (value "~")
      (footprint "easyedapro:CONN-TH_6P_PH2.0D-L-6P")
      (fields (field (name "Manufacturer Part") "PH2.0D-L-6P"))
      (libsource (lib "easyedapro") (part "PH2.0D-L-6P"))
    )
    (comp (ref "C12")
      (value "22uF")
      (footprint "easyedapro:CAP-TH_BD5.0-P2.00-D0.6-FD")
      (fields
        (field (name "Manufacturer Part") "LW220M0500511PV2-D5")
        (field (name "Manufacturer") "UNITED(怡德)")
      )
      (libsource (lib "easyedapro") (part "LW220M0500511PV2-D5"))
    )
    (comp (ref "C13")
      (value "100nF")
      (footprint "easyedapro:C0805")
      (fields (field (name "Manufacturer Part") "0805"))
      (libsource (lib "easyedapro") (part "0805_C9900012713"))
    )
    (comp (ref "C14")
      (value "10uF")
      (footprint "easyedapro:CAP-TH_BD5.0-P2.00-D0.8-FD")
      (fields
        (field (name "Manufacturer Part") "KM106M025D11RR0VH2FP0")
        (field (name "Manufacturer") "CX(承兴)")
      )
      (libsource (lib "easyedapro") (part "10uF 25V 5*11"))
    )
    (comp (ref "C15")
      (value "100nF/50V")
      (footprint "easyedapro:C0805")
      (fields (field (name "Manufacturer Part") "0805"))
      (libsource (lib "easyedapro") (part "0805_C9900012713"))
    )
    (comp (ref "C16")
      (value "330nF/50V")
      (footprint "easyedapro:C0805")
      (fields (field (name "Manufacturer Part") "0805"))
      (libsource (lib "easyedapro") (part "0805_C9900012713"))
    )
    (comp (ref "DC1")
      (value "12V")
      (footprint "easyedapro:DC-IN-TH_DC005-T20")
      (description "连接器类型:DC电源插座;安装方式:弯插;触点内径:-;触点外径:6.3mm;额定电流:3A;额定电压:30V;工作温度范围:-10~+60;")
      (fields (field (name "Manufacturer Part") "DC005-T20") (field (name "Manufacturer") "SOFNG(硕方)"))
      (libsource (lib "easyedapro") (part "DC005-2.0MM"))
    )
    (comp (ref "LED1")
      (value "电源")
      (footprint "easyedapro:LED0805-R-RD")
      (description "发光颜色:翠绿;")
      (fields (field (name "Manufacturer Part") "NCD0805G1") (field (name "Manufacturer") "国星光电"))
      (libsource (lib "easyedapro") (part "FC-2012UGK-520D5"))
    )
    (comp (ref "R20")
      (value "4.7K")
      (footprint "easyedapro:R0805")
      (fields (field (name "Manufacturer Part") "0805"))
      (libsource (lib "easyedapro") (part "0805"))
    )
    (comp (ref "SW3")
      (value "~")
      (footprint "easyedapro:SW-TH_6P-L16.5-W7.5-P4.0-LS2.6-TL")
      (fields (field (name "Manufacturer Part") "SS-22F08-G012") (field (name "Manufacturer") "G-Switch(品赞)"))
      (libsource (lib "easyedapro") (part "SS-22F08-G012"))
    )
    (comp (ref "U4")
      (value "~")
      (footprint "easyedapro:TO-252-2_L6.5-W6.1-P4.58-LS10.0-TL")
      (fields (field (name "Manufacturer Part") "78M05") (field (name "Manufacturer") "集晶电子"))
      (libsource (lib "easyedapro") (part "78M05_C2984682"))
    )
    (comp (ref "U6")
      (value "AMS1117-3V3")
      (footprint "easyedapro:SOT-223-3_L6.7-W3.7-P2.30-LS7.0-BR")
      (description "静态电流(Iq):-;输出类型:固定;最大输入电压:18V;输出电压(可调):-;压降(max):1.5V @ 1A;输出电压(固定):5V;")
      (fields (field (name "Manufacturer Part") "AMS1117-5.0") (field (name "Manufacturer") "Slkor(萨科微)"))
      (libsource (lib "easyedapro") (part "AMS1117-5.0_C473812"))
    )
    (comp (ref "H6")
      (value "A2541WV-2x4P")
      (footprint "easyedapro:HDR-TH_8P-P2.54-V-R2-C4-S2.54_A2541WV-2X4P")
      (fields (field (name "Manufacturer") "CJT(长江连接器)"))
      (libsource (lib "easyedapro") (part "A2541WV-2X4P"))
    )
  )
  (nets
    (net (code "1") (name "3V3") (class "Default")
      (node (ref "C1") (pin "1") (pinfunction "1_1") (pintype "input"))
      (node (ref "C12") (pin "1") (pinfunction "1_1") (pintype "input"))
      (node (ref "C2") (pin "1") (pinfunction "1_1") (pintype "input"))
      (node (ref "C20") (pin "1") (pinfunction "1_1") (pintype "input"))
      (node (ref "C21") (pin "1") (pinfunction "1_1") (pintype "input"))
      (node (ref "C22") (pin "1") (pinfunction "1_1") (pintype "input"))
      (node (ref "C3") (pin "1") (pinfunction "1_1") (pintype "input"))
      (node (ref "C4") (pin "1") (pinfunction "1_1") (pintype "input"))
      (node (ref "H1") (pin "1") (pinfunction "1_1") (pintype "input"))
      (node (ref "H5") (pin "1") (pinfunction "1_1") (pintype "input"))
      (node (ref "H6") (pin "7") (pinfunction "7_7") (pintype "input"))
      (node (ref "R12") (pin "2") (pinfunction "2_2") (pintype "input"))
      (node (ref "R2") (pin "1") (pinfunction "1_1") (pintype "input"))
      (node (ref "R3") (pin "1") (pinfunction "1_1") (pintype "input"))
      (node (ref "R8") (pin "2") (pinfunction "2_2") (pintype "input"))
      (node (ref "SW2") (pin "1") (pinfunction "1_1") (pintype "input"))
      (node (ref "SW2") (pin "2") (pinfunction "2_2") (pintype "input"))
      (node (ref "U1") (pin "1") (pinfunction "VBAT_1") (pintype "input"))
      (node (ref "U1") (pin "24") (pinfunction "VDD_1_24") (pintype "input"))
      (node (ref "U1") (pin "36") (pinfunction "VDD_2_36") (pintype "input"))
      (node (ref "U1") (pin "48") (pinfunction "VDD_3_48") (pintype "input"))
      (node (ref "U1") (pin "9") (pinfunction "VDDA_9") (pintype "input"))
      (node (ref "U2") (pin "13") (pinfunction "VDD_13") (pintype "input"))
      (node (ref "U2") (pin "8") (pinfunction "VLOGIC_8") (pintype "input"))
      (node (ref "U5") (pin "5") (pinfunction "5_5") (pintype "input"))
      (node (ref "U6") (pin "2") (pinfunction "VOUT_2") (pintype "input"))
      (node (ref "U6") (pin "4") (pinfunction "VOUT_4") (pintype "input"))
      (node (ref "U8") (pin "5") (pinfunction "5_5") (pintype "input"))
    )
    (net (code "2") (name "5V") (class "Default")
      (node (ref "C10") (pin "1") (pinfunction "1_1") (pintype "input"))
      (node (ref "C15") (pin "1") (pinfunction "1_1") (pintype "input"))
      (node (ref "C23") (pin "1") (pinfunction "1_1") (pintype "input"))
      (node (ref "U3") (pin "11") (pinfunction "Enable_B_11") (pintype "input"))
      (node (ref "U3") (pin "6") (pinfunction "Enable_A_6") (pintype "input"))
      (node (ref "U3") (pin "9") (pinfunction "VSS_9") (pintype "input"))
      (node (ref "U4") (pin "3") (pinfunction "OUT_3") (pintype "input"))
    )
    (net (code "3") (name "24L01_CE") (class "Default")
      (node (ref "H6") (pin "6") (pinfunction "6_6") (pintype "input"))
      (node (ref "U1") (pin "14") (pinfunction "PA4_14") (pintype "input"))
    )
    (net (code "4") (name "24L01_CSN") (class "Default")
      (node (ref "H6") (pin "5") (pinfunction "5_5") (pintype "input"))
      (node (ref "U1") (pin "13") (pinfunction "PA3_13") (pintype "input"))
    )
    (net (code "5") (name "24L01_IRQ") (class "Default")
      (node (ref "H6") (pin "1") (pinfunction "1_1") (pintype "input"))
      (node (ref "U1") (pin "12") (pinfunction "PA2_12") (pintype "input"))
    )
    (net (code "6") (name "24L01_MISO") (class "Default")
      (node (ref "H6") (pin "2") (pinfunction "2_2") (pintype "input"))
      (node (ref "U1") (pin "27") (pinfunction "PB14_27") (pintype "input"))
    )
    (net (code "7") (name "24L01_MOSI") (class "Default")
      (node (ref "H6") (pin "3") (pinfunction "3_3") (pintype "input"))
      (node (ref "U1") (pin "28") (pinfunction "PB15_28") (pintype "input"))
    )
    (net (code "8") (name "24L01_SCK") (class "Default")
      (node (ref "H6") (pin "4") (pinfunction "4_4") (pintype "input"))
      (node (ref "U1") (pin "26") (pinfunction "PB13_26") (pintype "input"))
    )
    (net (code "9") (name "BOOT0") (class "Default")
      (node (ref "R11") (pin "2") (pinfunction "2_2") (pintype "input"))
      (node (ref "R9") (pin "2") (pinfunction "2_2") (pintype "input"))
      (node (ref "U1") (pin "44") (pinfunction "BOOT0_44") (pintype "input"))
    )
    (net (code "10") (name "BOOT1") (class "Default")
      (node (ref "R10") (pin "2") (pinfunction "2_2") (pintype "input"))
      (node (ref "U1") (pin "19") (pinfunction "PB1_19") (pintype "input"))
    )
    (net (code "11") (name "EN_KEY") (class "Default")
      (node (ref "SW4") (pin "3") (pinfunction "3_3") (pintype "input"))
      (node (ref "SW4") (pin "4") (pinfunction "4_4") (pintype "input"))
      (node (ref "U1") (pin "20") (pinfunction "PB2_20") (pintype "input"))
    )
    (net (code "12") (name "GND") (class "Default")
      (node (ref "C1") (pin "2") (pinfunction "2_2") (pintype "input"))
      (node (ref "C10") (pin "2") (pinfunction "2_2") (pintype "input"))
      (node (ref "C12") (pin "2") (pinfunction "2_2") (pintype "input"))
      (node (ref "C13") (pin "2") (pinfunction "2_2") (pintype "input"))
      (node (ref "C14") (pin "2") (pinfunction "2_2") (pintype "input"))
      (node (ref "C15") (pin "2") (pinfunction "2_2") (pintype "input"))
      (node (ref "C16") (pin "2") (pinfunction "2_2") (pintype "input"))
      (node (ref "C19") (pin "2") (pinfunction "2_2") (pintype "input"))
      (node (ref "C2") (pin "2") (pinfunction "2_2") (pintype "input"))
      (node (ref "C20") (pin "2") (pinfunction "2_2") (pintype "input"))
      (node (ref "C21") (pin "2") (pinfunction "2_2") (pintype "input"))
      (node (ref "C22") (pin "2") (pinfunction "2_2") (pintype "input"))
      (node (ref "C23") (pin "2") (pinfunction "2_2") (pintype "input"))
      (node (ref "C24") (pin "2") (pinfunction "2_2") (pintype "input"))
      (node (ref "C3") (pin "2") (pinfunction "2_2") (pintype "input"))
      (node (ref "C4") (pin "2") (pinfunction "2_2") (pintype "input"))
      (node (ref "C5") (pin "2") (pinfunction "2_2") (pintype "input"))
      (node (ref "C6") (pin "2") (pinfunction "2_2") (pintype "input"))
      (node (ref "C7") (pin "1") (pinfunction "1_1") (pintype "input"))
      (node (ref "C8") (pin "2") (pinfunction "2_2") (pintype "input"))
      (node (ref "C9") (pin "2") (pinfunction "2_2") (pintype "input"))
      (node (ref "D2") (pin "2") (pinfunction "A_2") (pintype "input"))
      (node (ref "D4") (pin "2") (pinfunction "A_2") (pintype "input"))
      (node (ref "D6") (pin "2") (pinfunction "A_2") (pintype "input"))
      (node (ref "D8") (pin "2") (pinfunction "A_2") (pintype "input"))
      (node (ref "H1") (pin "4") (pinfunction "4_4") (pintype "input"))
      (node (ref "H2") (pin "3") (pinfunction "3_3") (pintype "input"))
      (node (ref "H5") (pin "2") (pinfunction "2_2") (pintype "input"))
      (node (ref "H6") (pin "8") (pinfunction "8_8") (pintype "input"))
      (node (ref "R10") (pin "1") (pinfunction "1_1") (pintype "input"))
      (node (ref "R13") (pin "2") (pinfunction "2_2") (pintype "input"))
      (node (ref "R20") (pin "2") (pinfunction "2_2") (pintype "input"))
      (node (ref "R29") (pin "2") (pinfunction "2_2") (pintype "input"))
      (node (ref "R4") (pin "1") (pinfunction "1_1") (pintype "input"))
      (node (ref "R9") (pin "1") (pinfunction "1_1") (pintype "input"))
      (node (ref "SW1") (pin "1") (pinfunction "1_1") (pintype "input"))
      (node (ref "SW1") (pin "2") (pinfunction "2_2") (pintype "input"))
      (node (ref "SW3") (pin "5") (pinfunction "5_5") (pintype "input"))
      (node (ref "SW3") (pin "7") (pinfunction "7_7") (pintype "input"))
      (node (ref "SW3") (pin "8") (pinfunction "8_8") (pintype "input"))
      (node (ref "SW4") (pin "1") (pinfunction "1_1") (pintype "input"))
      (node (ref "SW4") (pin "2") (pinfunction "2_2") (pintype "input"))
      (node (ref "U1") (pin "23") (pinfunction "VSS_1_23") (pintype "input"))
      (node (ref "U1") (pin "35") (pinfunction "VSS_2_35") (pintype "input"))
      (node (ref "U1") (pin "47") (pinfunction "VSS_3_47") (pintype "input"))
      (node (ref "U1") (pin "8") (pinfunction "VSSA_8") (pintype "input"))
      (node (ref "U2") (pin "1") (pinfunction "CLKIN_1") (pintype "input"))
      (node (ref "U2") (pin "11") (pinfunction "FSYNC_11") (pintype "input"))
      (node (ref "U2") (pin "18") (pinfunction "GND_18") (pintype "input"))
      (node (ref "U2") (pin "25") (pinfunction "GND_25") (pintype "input"))
      (node (ref "U3") (pin "1") (pinfunction "Sense_A_1") (pintype "input"))
      (node (ref "U3") (pin "15") (pinfunction "Sense_B_15") (pintype "input"))
      (node (ref "U3") (pin "8") (pinfunction "GND_8") (pintype "input"))
      (node (ref "U4") (pin "4") (pinfunction "GND_4") (pintype "input"))
      (node (ref "U5") (pin "2") (pinfunction "2_2") (pintype "input"))
      (node (ref "U6") (pin "1") (pinfunction "ADJ/GND_1") (pintype "input"))
      (node (ref "U8") (pin "2") (pinfunction "2_2") (pintype "input"))
    )
    (net (code "13") (name "I2C_SCL") (class "Default")
      (node (ref "H5") (pin "3") (pinfunction "3_3") (pintype "input"))
      (node (ref "R3") (pin "2") (pinfunction "2_2") (pintype "input"))
      (node (ref "U1") (pin "45") (pinfunction "PB8_45") (pintype "input"))
      (node (ref "U2") (pin "23") (pinfunction "SCL_23") (pintype "input"))
    )
    (net (code "14") (name "I2C_SDA") (class "Default")
      (node (ref "H5") (pin "4") (pinfunction "4_4") (pintype "input"))
      (node (ref "R2") (pin "2") (pinfunction "2_2") (pintype "input"))
      (node (ref "U1") (pin "46") (pinfunction "PB9_46") (pintype "input"))
      (node (ref "U2") (pin "24") (pinfunction "SDA_24") (pintype "input"))
    )
    (net (code "15") (name "LED_EN") (class "Default")
      (node (ref "LED5") (pin "1") (pinfunction "A_1") (pintype "input"))
      (node (ref "U1") (pin "15") (pinfunction "PA5_15") (pintype "input"))
    )
    (net (code "16") (name "L_ENCODER_A") (class "Default")
      (node (ref "U1") (pin "10") (pinfunction "PA0-WKUP_10") (pintype "input"))
      (node (ref "U8") (pin "3") (pinfunction "3_3") (pintype "input"))
    )
    (net (code "17") (name "L_ENCODER_B") (class "Default")
      (node (ref "U1") (pin "11") (pinfunction "PA1_11") (pintype "input"))
      (node (ref "U8") (pin "4") (pinfunction "4_4") (pintype "input"))
    )
    (net (code "18") (name "MPU6050_AD0") (class "Default")
      (node (ref "R4") (pin "2") (pinfunction "2_2") (pintype "input"))
      (node (ref "U2") (pin "9") (pinfunction "AD0_9") (pintype "input"))
    )
    (net (code "19") (name "M_L1") (class "Default")
      (node (ref "D1") (pin "2") (pinfunction "A_2") (pintype "input"))
      (node (ref "D2") (pin "1") (pinfunction "K_1") (pintype "input"))
      (node (ref "U3") (pin "2") (pinfunction "OUT_1_2") (pintype "input"))
      (node (ref "U8") (pin "1") (pinfunction "1_1") (pintype "input"))
    )
    (net (code "20") (name "M_L2") (class "Default")
      (node (ref "D3") (pin "2") (pinfunction "A_2") (pintype "input"))
      (node (ref "D4") (pin "1") (pinfunction "K_1") (pintype "input"))
      (node (ref "U3") (pin "3") (pinfunction "OUT_2_3") (pintype "input"))
      (node (ref "U8") (pin "6") (pinfunction "6_6") (pintype "input"))
    )
    (net (code "21") (name "M_R1") (class "Default")
      (node (ref "D5") (pin "2") (pinfunction "A_2") (pintype "input"))
      (node (ref "D6") (pin "1") (pinfunction "K_1") (pintype "input"))
      (node (ref "U3") (pin "13") (pinfunction "Out3_13") (pintype "input"))
      (node (ref "U5") (pin "1") (pinfunction "1_1") (pintype "input"))
    )
    (net (code "22") (name "M_R2") (class "Default")
      (node (ref "D7") (pin "2") (pinfunction "A_2") (pintype "input"))
      (node (ref "D8") (pin "1") (pinfunction "K_1") (pintype "input"))
      (node (ref "U3") (pin "14") (pinfunction "Out4_14") (pintype "input"))
      (node (ref "U5") (pin "6") (pinfunction "6_6") (pintype "input"))
    )
    (net (code "23") (name "NRST") (class "Default")
      (node (ref "C19") (pin "1") (pinfunction "1_1") (pintype "input"))
      (node (ref "R8") (pin "1") (pinfunction "1_1") (pintype "input"))
      (node (ref "SW1") (pin "3") (pinfunction "3_3") (pintype "input"))
      (node (ref "SW1") (pin "4") (pinfunction "4_4") (pintype "input"))
      (node (ref "U1") (pin "7") (pinfunction "NRST_7") (pintype "input"))
    )
    (net (code "24") (name "Net-(DC1-Pad1)") (class "Default")
      (node (ref "DC1") (pin "1") (pinfunction "1_1") (pintype "input"))
      (node (ref "SW3") (pin "1") (pinfunction "1_1") (pintype "input"))
    )
    (net (code "25") (name "Net-(DC1-Pad2)") (class "Default")
      (node (ref "DC1") (pin "2") (pinfunction "2_2") (pintype "input"))
      (node (ref "DC1") (pin "3") (pinfunction "3_3") (pintype "input"))
      (node (ref "SW3") (pin "4") (pinfunction "4_4") (pintype "input"))
    )
    (net (code "26") (name "Net-(LED1-K)") (class "Default")
      (node (ref "LED1") (pin "2") (pinfunction "K_2") (pintype "input"))
      (node (ref "R20") (pin "1") (pinfunction "1_1") (pintype "input"))
    )
    (net (code "27") (name "Net-(LED5-K)") (class "Default")
      (node (ref "LED5") (pin "2") (pinfunction "K_2") (pintype "input"))
      (node (ref "R29") (pin "1") (pinfunction "1_1") (pintype "input"))
    )
    (net (code "28") (name "Net-(R11-Pad1)") (class "Default")
      (node (ref "R11") (pin "1") (pinfunction "1_1") (pintype "input"))
      (node (ref "SW2") (pin "3") (pinfunction "3_3") (pintype "input"))
      (node (ref "SW2") (pin "4") (pinfunction "4_4") (pintype "input"))
    )
    (net (code "29") (name "Net-(U2-CPOUT)") (class "Default")
      (node (ref "C8") (pin "1") (pinfunction "1_1") (pintype "input"))
      (node (ref "U2") (pin "20") (pinfunction "CPOUT_20") (pintype "input"))
    )
    (net (code "30") (name "Net-(U2-REGOUT)") (class "Default")
      (node (ref "C7") (pin "2") (pinfunction "2_2") (pintype "input"))
      (node (ref "U2") (pin "10") (pinfunction "REGOUT_10") (pintype "input"))
    )
    (net (code "31") (name "OSC_IN") (class "Default")
      (node (ref "C5") (pin "1") (pinfunction "1_1") (pintype "input"))
      (node (ref "U1") (pin "5") (pinfunction "PD0-OSC_IN_5") (pintype "input"))
      (node (ref "X1") (pin "1") (pinfunction "OSC1_1") (pintype "input"))
    )
    (net (code "32") (name "OSC_OUT") (class "Default")
      (node (ref "C6") (pin "1") (pinfunction "1_1") (pintype "input"))
      (node (ref "U1") (pin "6") (pinfunction "PD1-OSC_OUT_6") (pintype "input"))
      (node (ref "X1") (pin "2") (pinfunction "OSC2_2") (pintype "input"))
    )
    (net (code "33") (name "PWM_L1") (class "Default")
      (node (ref "U1") (pin "29") (pinfunction "PA8_29") (pintype "input"))
      (node (ref "U3") (pin "5") (pinfunction "Input_1_5") (pintype "input"))
    )
    (net (code "34") (name "PWM_L2") (class "Default")
      (node (ref "U1") (pin "30") (pinfunction "PA9_30") (pintype "input"))
      (node (ref "U3") (pin "7") (pinfunction "Input_2_7") (pintype "input"))
    )
    (net (code "35") (name "PWM_R1") (class "Default")
      (node (ref "U1") (pin "31") (pinfunction "PA10_31") (pintype "input"))
      (node (ref "U3") (pin "10") (pinfunction "Input_3_10") (pintype "input"))
    )
    (net (code "36") (name "PWM_R2") (class "Default")
      (node (ref "U1") (pin "32") (pinfunction "PA11_32") (pintype "input"))
      (node (ref "U3") (pin "12") (pinfunction "Input_4_12") (pintype "input"))
    )
    (net (code "37") (name "RDX") (class "Default")
      (node (ref "H2") (pin "1") (pinfunction "1_1") (pintype "input"))
      (node (ref "U1") (pin "43") (pinfunction "PB7_43") (pintype "input"))
    )
    (net (code "38") (name "R_ENCODER_A") (class "Default")
      (node (ref "U1") (pin "16") (pinfunction "PA6_16") (pintype "input"))
      (node (ref "U5") (pin "3") (pinfunction "3_3") (pintype "input"))
    )
    (net (code "39") (name "R_ENCODER_B") (class "Default")
      (node (ref "U1") (pin "17") (pinfunction "PA7_17") (pintype "input"))
      (node (ref "U5") (pin "4") (pinfunction "4_4") (pintype "input"))
    )
    (net (code "40") (name "SWCLK") (class "Default")
      (node (ref "H1") (pin "3") (pinfunction "3_3") (pintype "input"))
      (node (ref "R13") (pin "1") (pinfunction "1_1") (pintype "input"))
      (node (ref "U1") (pin "37") (pinfunction "PA14_37") (pintype "input"))
    )
    (net (code "41") (name "SWDIO") (class "Default")
      (node (ref "H1") (pin "2") (pinfunction "2_2") (pintype "input"))
      (node (ref "R12") (pin "1") (pinfunction "1_1") (pintype "input"))
      (node (ref "U1") (pin "34") (pinfunction "PA13_34") (pintype "input"))
    )
    (net (code "42") (name "TDX") (class "Default")
      (node (ref "H2") (pin "2") (pinfunction "2_2") (pintype "input"))
      (node (ref "U1") (pin "42") (pinfunction "PB6_42") (pintype "input"))
    )
    (net (code "43") (name "VCC") (class "Default")
      (node (ref "C13") (pin "1") (pinfunction "1_1") (pintype "input"))
      (node (ref "C14") (pin "1") (pinfunction "1_1") (pintype "input"))
      (node (ref "C16") (pin "1") (pinfunction "1_1") (pintype "input"))
      (node (ref "C24") (pin "1") (pinfunction "1_1") (pintype "input"))
      (node (ref "C9") (pin "1") (pinfunction "1_1") (pintype "input"))
      (node (ref "D1") (pin "1") (pinfunction "K_1") (pintype "input"))
      (node (ref "D3") (pin "1") (pinfunction "K_1") (pintype "input"))
      (node (ref "D5") (pin "1") (pinfunction "K_1") (pintype "input"))
      (node (ref "D7") (pin "1") (pinfunction "K_1") (pintype "input"))
      (node (ref "LED1") (pin "1") (pinfunction "A_1") (pintype "input"))
      (node (ref "SW3") (pin "2") (pinfunction "2_2") (pintype "input"))
      (node (ref "U3") (pin "4") (pinfunction "VS_4") (pintype "input"))
      (node (ref "U4") (pin "1") (pinfunction "IN_1") (pintype "input"))
      (node (ref "U6") (pin "3") (pinfunction "VIN_3") (pintype "input"))
    )
    (net (code "44") (name "unconnected-(H5-Pad5)") (class "Default")
      (node (ref "H5") (pin "5") (pinfunction "5_5") (pintype "input+no_connect"))
    )
    (net (code "45") (name "unconnected-(H5-Pad6)") (class "Default")
      (node (ref "H5") (pin "6") (pinfunction "6_6") (pintype "input+no_connect"))
    )
    (net (code "46") (name "unconnected-(H5-Pad7)") (class "Default")
      (node (ref "H5") (pin "7") (pinfunction "7_7") (pintype "input+no_connect"))
    )
    (net (code "47") (name "unconnected-(H5-Pad8)") (class "Default")
      (node (ref "H5") (pin "8") (pinfunction "8_8") (pintype "input+no_connect"))
    )
    (net (code "48") (name "unconnected-(SW3-Pad3)") (class "Default")
      (node (ref "SW3") (pin "3") (pinfunction "3_3") (pintype "input+no_connect"))
    )
    (net (code "49") (name "unconnected-(SW3-Pad6)") (class "Default")
      (node (ref "SW3") (pin "6") (pinfunction "6_6") (pintype "input+no_connect"))
    )
    (net (code "50") (name "unconnected-(U1-PA12-Pad33)") (class "Default")
      (node (ref "U1") (pin "33") (pinfunction "PA12_33") (pintype "input+no_connect"))
    )
    (net (code "51") (name "unconnected-(U1-PA15-Pad38)") (class "Default")
      (node (ref "U1") (pin "38") (pinfunction "PA15_38") (pintype "input+no_connect"))
    )
    (net (code "52") (name "unconnected-(U1-PB0-Pad18)") (class "Default")
      (node (ref "U1") (pin "18") (pinfunction "PB0_18") (pintype "input+no_connect"))
    )
    (net (code "53") (name "unconnected-(U1-PB3-Pad39)") (class "Default")
      (node (ref "U1") (pin "39") (pinfunction "PB3_39") (pintype "input+no_connect"))
    )
    (net (code "54") (name "unconnected-(U1-PB4-Pad40)") (class "Default")
      (node (ref "U1") (pin "40") (pinfunction "PB4_40") (pintype "input+no_connect"))
    )
    (net (code "55") (name "unconnected-(U1-PB5-Pad41)") (class "Default")
      (node (ref "U1") (pin "41") (pinfunction "PB5_41") (pintype "input+no_connect"))
    )
    (net (code "56") (name "unconnected-(U1-PB10-Pad21)") (class "Default")
      (node (ref "U1") (pin "21") (pinfunction "PB10_21") (pintype "input+no_connect"))
    )
    (net (code "57") (name "unconnected-(U1-PB11-Pad22)") (class "Default")
      (node (ref "U1") (pin "22") (pinfunction "PB11_22") (pintype "input+no_connect"))
    )
    (net (code "58") (name "unconnected-(U1-PB12-Pad25)") (class "Default")
      (node (ref "U1") (pin "25") (pinfunction "PB12_25") (pintype "input+no_connect"))
    )
    (net (code "59") (name "unconnected-(U1-PC13-TAMPER-RTC-Pad2)") (class "Default")
      (node (ref "U1") (pin "2") (pinfunction "PC13-TAMPER-RTC_2") (pintype "input+no_connect"))
    )
    (net (code "60") (name "unconnected-(U1-PC14-OSC32_IN-Pad3)") (class "Default")
      (node (ref "U1") (pin "3") (pinfunction "PC14-OSC32_IN_3") (pintype "input+no_connect"))
    )
    (net (code "61") (name "unconnected-(U1-PC15-OSC32_OUT-Pad4)") (class "Default")
      (node (ref "U1") (pin "4") (pinfunction "PC15-OSC32_OUT_4") (pintype "input+no_connect"))
    )
    (net (code "62") (name "unconnected-(U2-AUX_CL-Pad7)") (class "Default")
      (node (ref "U2") (pin "7") (pinfunction "AUX_CL_7") (pintype "input+no_connect"))
    )
    (net (code "63") (name "unconnected-(U2-AUX_DA-Pad6)") (class "Default")
      (node (ref "U2") (pin "6") (pinfunction "AUX_DA_6") (pintype "input+no_connect"))
    )
    (net (code "64") (name "unconnected-(U2-INT-Pad12)") (class "Default")
      (node (ref "U2") (pin "12") (pinfunction "INT_12") (pintype "input+no_connect"))
    )
    (net (code "65") (name "unconnected-(U2-NC-Pad2)") (class "Default")
      (node (ref "U2") (pin "2") (pinfunction "NC_2") (pintype "input+no_connect"))
    )
    (net (code "66") (name "unconnected-(U2-NC-Pad3)") (class "Default")
      (node (ref "U2") (pin "3") (pinfunction "NC_3") (pintype "input+no_connect"))
    )
    (net (code "67") (name "unconnected-(U2-NC-Pad4)") (class "Default")
      (node (ref "U2") (pin "4") (pinfunction "NC_4") (pintype "input+no_connect"))
    )
    (net (code "68") (name "unconnected-(U2-NC-Pad5)") (class "Default")
      (node (ref "U2") (pin "5") (pinfunction "NC_5") (pintype "input+no_connect"))
    )
    (net (code "69") (name "unconnected-(U2-NC-Pad14)") (class "Default")
      (node (ref "U2") (pin "14") (pinfunction "NC_14") (pintype "input"))
    )
    (net (code "70") (name "unconnected-(U2-NC-Pad15)") (class "Default")
      (node (ref "U2") (pin "15") (pinfunction "NC_15") (pintype "input"))
    )
    (net (code "71") (name "unconnected-(U2-NC-Pad16)") (class "Default")
      (node (ref "U2") (pin "16") (pinfunction "NC_16") (pintype "input"))
    )
    (net (code "72") (name "unconnected-(U2-NC-Pad17)") (class "Default")
      (node (ref "U2") (pin "17") (pinfunction "NC_17") (pintype "input"))
    )
    (net (code "73") (name "unconnected-(U2-RESV-Pad19)") (class "Default")
      (node (ref "U2") (pin "19") (pinfunction "RESV_19") (pintype "input"))
    )
    (net (code "74") (name "unconnected-(U2-RESV-Pad21)") (class "Default")
      (node (ref "U2") (pin "21") (pinfunction "RESV_21") (pintype "input"))
    )
    (net (code "75") (name "unconnected-(U2-RESV-Pad22)") (class "Default")
      (node (ref "U2") (pin "22") (pinfunction "RESV_22") (pintype "input"))
    )
  )
)
